# falownik_2.net
KiCad netlist of a schematic drawn in EAGLE
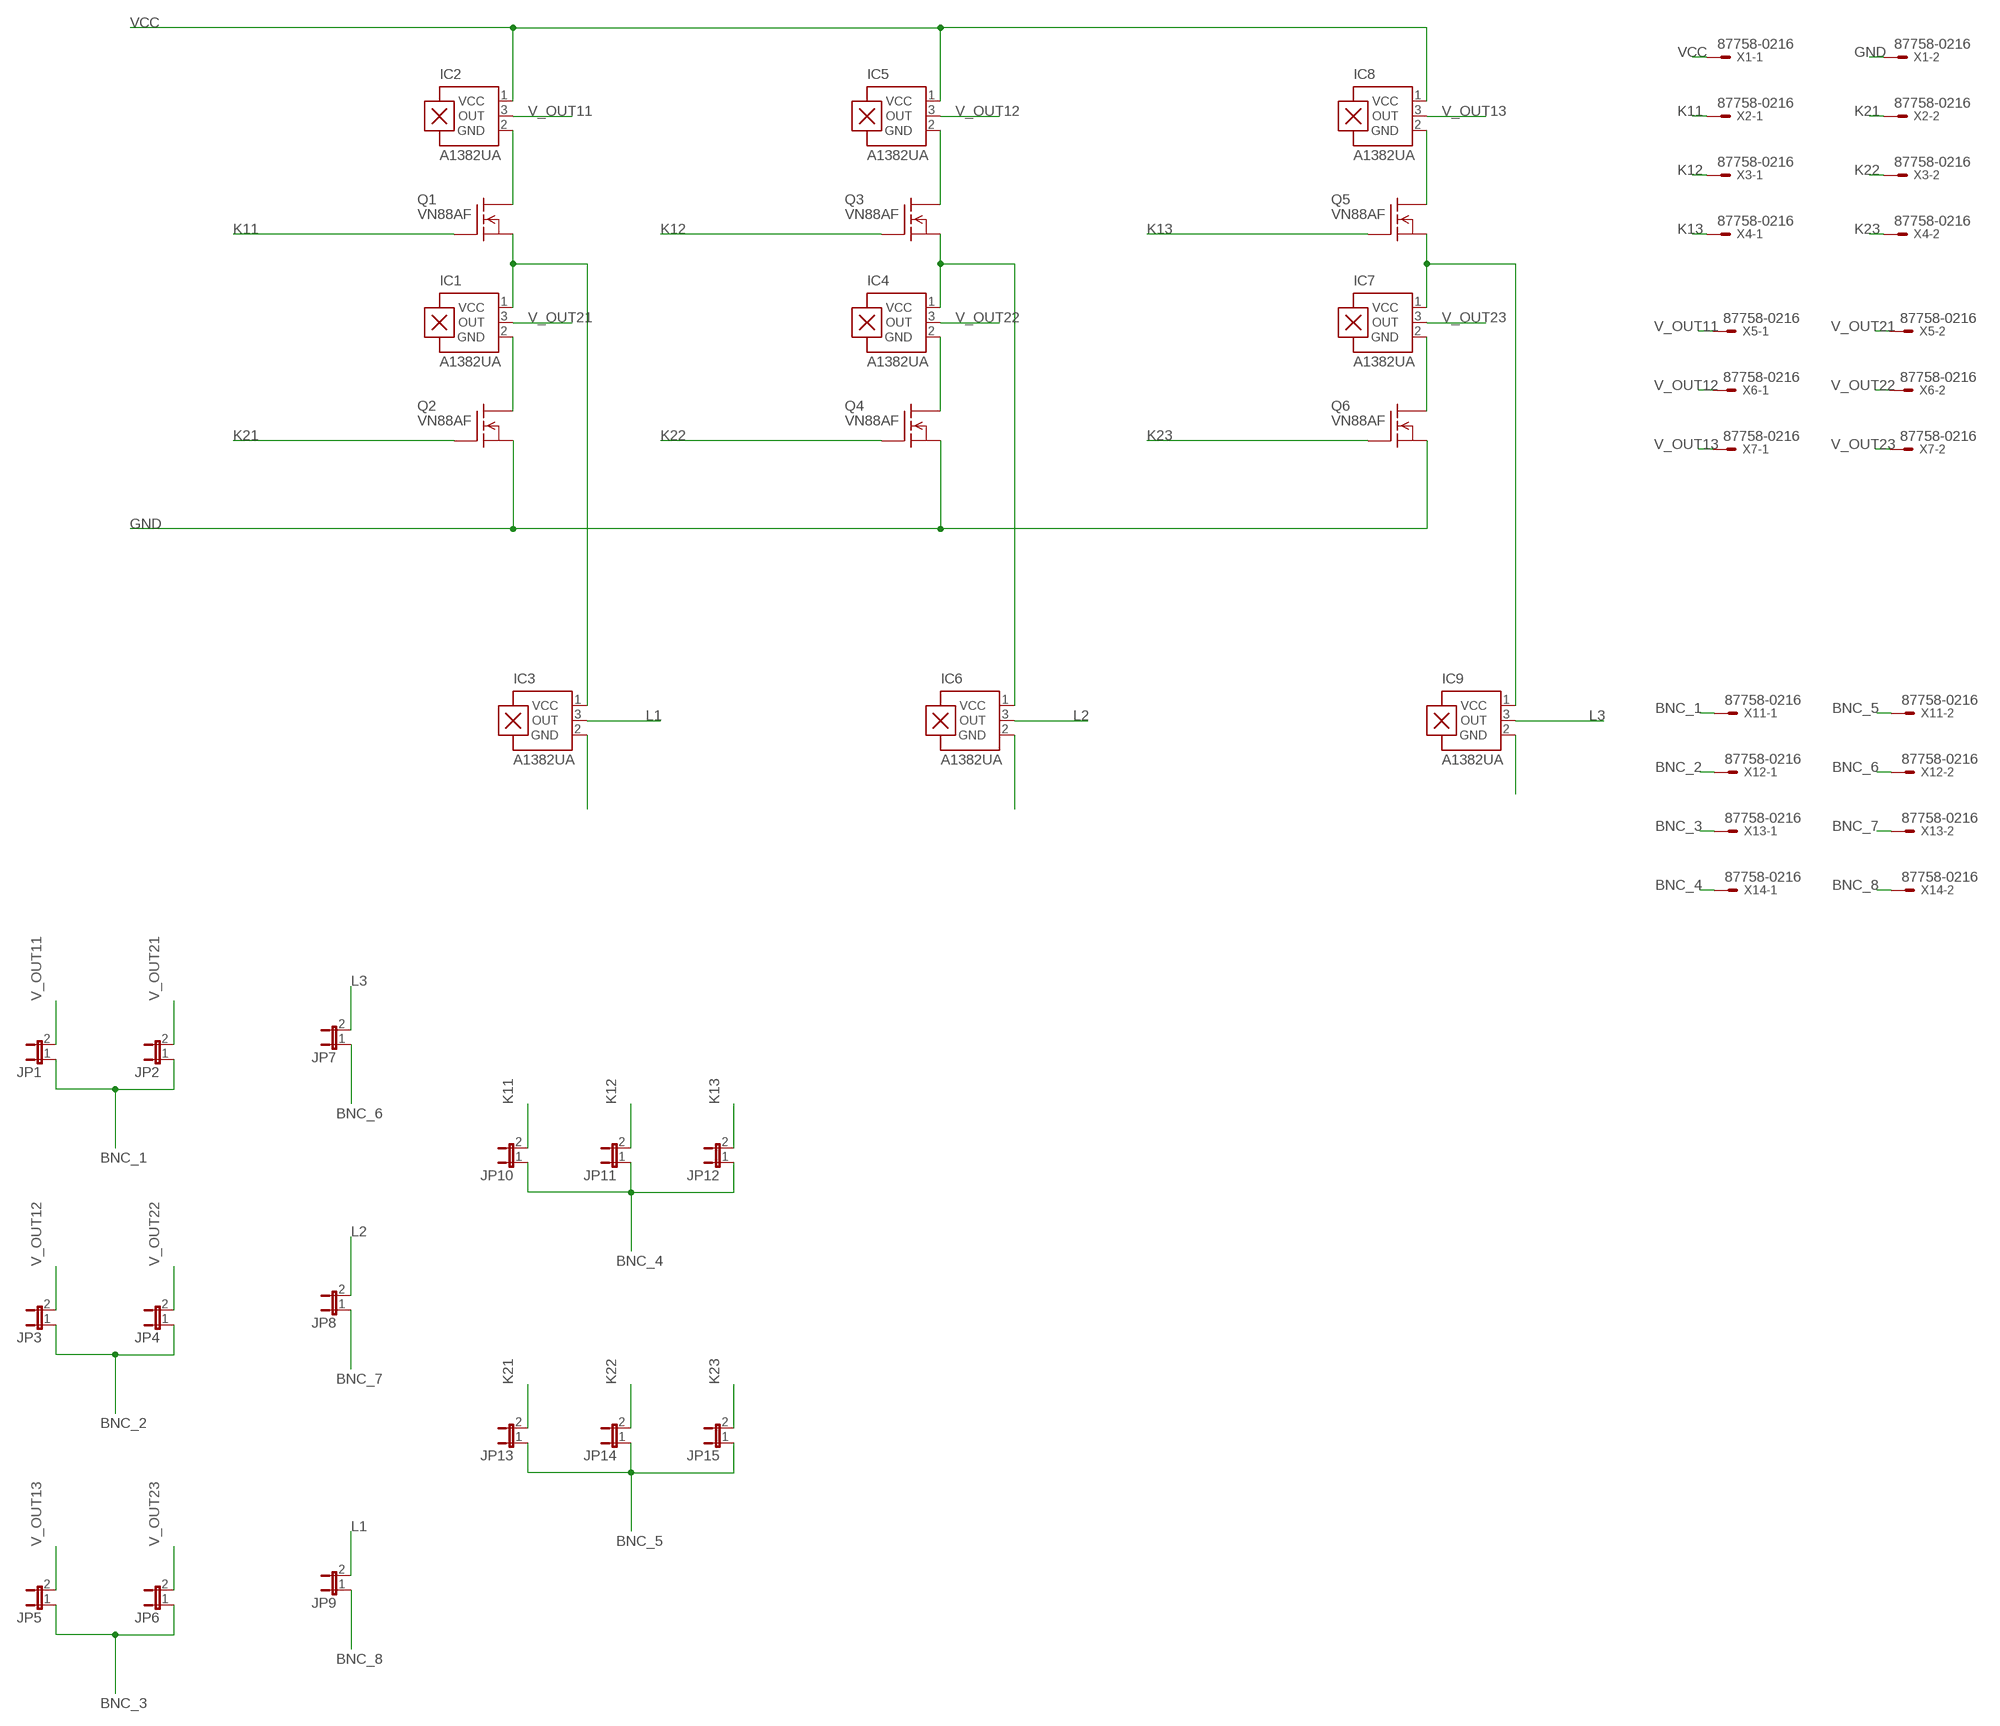
[diagram p0: schematic, sheet 1]

(export (version "E")
  (design (tool "Eeschema 10.0.6"))
  (components
    (comp (ref "IC1")
      (value "A1382UA")
      (footprint "eagle-import:SIP3-UA")
      (fields (field (name "MPN") "A1382LUA-T"))
      (libsource (lib "eagle-import") (part "A13?UA82"))
    )
    (comp (ref "IC2")
      (value "A1382UA")
      (footprint "eagle-import:SIP3-UA")
      (fields (field (name "MPN") "A1382LUA-T"))
      (libsource (lib "eagle-import") (part "A13?UA82"))
    )
    (comp (ref "IC3")
      (value "A1382UA")
      (footprint "eagle-import:SIP3-UA")
      (fields (field (name "MPN") "A1382LUA-T"))
      (libsource (lib "eagle-import") (part "A13?UA82"))
    )
    (comp (ref "IC4")
      (value "A1382UA")
      (footprint "eagle-import:SIP3-UA")
      (fields (field (name "MPN") "A1382LUA-T"))
      (libsource (lib "eagle-import") (part "A13?UA82"))
    )
    (comp (ref "IC5")
      (value "A1382UA")
      (footprint "eagle-import:SIP3-UA")
      (fields (field (name "MPN") "A1382LUA-T"))
      (libsource (lib "eagle-import") (part "A13?UA82"))
    )
    (comp (ref "IC6")
      (value "A1382UA")
      (footprint "eagle-import:SIP3-UA")
      (fields (field (name "MPN") "A1382LUA-T"))
      (libsource (lib "eagle-import") (part "A13?UA82"))
    )
    (comp (ref "IC7")
      (value "A1382UA")
      (footprint "eagle-import:SIP3-UA")
      (fields (field (name "MPN") "A1382LUA-T"))
      (libsource (lib "eagle-import") (part "A13?UA82"))
    )
    (comp (ref "IC8")
      (value "A1382UA")
      (footprint "eagle-import:SIP3-UA")
      (fields (field (name "MPN") "A1382LUA-T"))
      (libsource (lib "eagle-import") (part "A13?UA82"))
    )
    (comp (ref "IC9")
      (value "A1382UA")
      (footprint "eagle-import:SIP3-UA")
      (fields (field (name "MPN") "A1382LUA-T"))
      (libsource (lib "eagle-import") (part "A13?UA82"))
    )
    (comp (ref "JP1")
      (value "JP1E")
      (footprint "eagle-import:JP1")
      (libsource (lib "eagle-import") (part "JP1E"))
    )
    (comp (ref "JP2")
      (value "JP1E")
      (footprint "eagle-import:JP1")
      (libsource (lib "eagle-import") (part "JP1E"))
    )
    (comp (ref "JP3")
      (value "JP1E")
      (footprint "eagle-import:JP1")
      (libsource (lib "eagle-import") (part "JP1E"))
    )
    (comp (ref "JP4")
      (value "JP1E")
      (footprint "eagle-import:JP1")
      (libsource (lib "eagle-import") (part "JP1E"))
    )
    (comp (ref "JP5")
      (value "JP1E")
      (footprint "eagle-import:JP1")
      (libsource (lib "eagle-import") (part "JP1E"))
    )
    (comp (ref "JP6")
      (value "JP1E")
      (footprint "eagle-import:JP1")
      (libsource (lib "eagle-import") (part "JP1E"))
    )
    (comp (ref "JP7")
      (value "JP1E")
      (footprint "eagle-import:JP1")
      (libsource (lib "eagle-import") (part "JP1E"))
    )
    (comp (ref "JP8")
      (value "JP1E")
      (footprint "eagle-import:JP1")
      (libsource (lib "eagle-import") (part "JP1E"))
    )
    (comp (ref "JP9")
      (value "JP1E")
      (footprint "eagle-import:JP1")
      (libsource (lib "eagle-import") (part "JP1E"))
    )
    (comp (ref "JP10")
      (value "JP1E")
      (footprint "eagle-import:JP1")
      (libsource (lib "eagle-import") (part "JP1E"))
    )
    (comp (ref "JP11")
      (value "JP1E")
      (footprint "eagle-import:JP1")
      (libsource (lib "eagle-import") (part "JP1E"))
    )
    (comp (ref "JP12")
      (value "JP1E")
      (footprint "eagle-import:JP1")
      (libsource (lib "eagle-import") (part "JP1E"))
    )
    (comp (ref "JP13")
      (value "JP1E")
      (footprint "eagle-import:JP1")
      (libsource (lib "eagle-import") (part "JP1E"))
    )
    (comp (ref "JP14")
      (value "JP1E")
      (footprint "eagle-import:JP1")
      (libsource (lib "eagle-import") (part "JP1E"))
    )
    (comp (ref "JP15")
      (value "JP1E")
      (footprint "eagle-import:JP1")
      (libsource (lib "eagle-import") (part "JP1E"))
    )
    (comp (ref "Q1")
      (value "VN88AF")
      (footprint "eagle-import:TO202")
      (libsource (lib "eagle-import") (part "VN88AF"))
    )
    (comp (ref "Q2")
      (value "VN88AF")
      (footprint "eagle-import:TO202")
      (libsource (lib "eagle-import") (part "VN88AF"))
    )
    (comp (ref "Q3")
      (value "VN88AF")
      (footprint "eagle-import:TO202")
      (libsource (lib "eagle-import") (part "VN88AF"))
    )
    (comp (ref "Q4")
      (value "VN88AF")
      (footprint "eagle-import:TO202")
      (libsource (lib "eagle-import") (part "VN88AF"))
    )
    (comp (ref "Q5")
      (value "VN88AF")
      (footprint "eagle-import:TO202")
      (libsource (lib "eagle-import") (part "VN88AF"))
    )
    (comp (ref "Q6")
      (value "VN88AF")
      (footprint "eagle-import:TO202")
      (libsource (lib "eagle-import") (part "VN88AF"))
    )
    (comp (ref "X1")
      (value "87758-0216")
      (footprint "eagle-import:87758-0216")
      (fields (field (name "MF") "MOLEX"))
      (libsource (lib "eagle-import") (part "87758-0216"))
    )
    (comp (ref "X2")
      (value "87758-0216")
      (footprint "eagle-import:87758-0216")
      (fields (field (name "MF") "MOLEX"))
      (libsource (lib "eagle-import") (part "87758-0216"))
    )
    (comp (ref "X3")
      (value "87758-0216")
      (footprint "eagle-import:87758-0216")
      (fields (field (name "MF") "MOLEX"))
      (libsource (lib "eagle-import") (part "87758-0216"))
    )
    (comp (ref "X4")
      (value "87758-0216")
      (footprint "eagle-import:87758-0216")
      (fields (field (name "MF") "MOLEX"))
      (libsource (lib "eagle-import") (part "87758-0216"))
    )
    (comp (ref "X5")
      (value "87758-0216")
      (footprint "eagle-import:87758-0216")
      (fields (field (name "MF") "MOLEX"))
      (libsource (lib "eagle-import") (part "87758-0216"))
    )
    (comp (ref "X6")
      (value "87758-0216")
      (footprint "eagle-import:87758-0216")
      (fields (field (name "MF") "MOLEX"))
      (libsource (lib "eagle-import") (part "87758-0216"))
    )
    (comp (ref "X7")
      (value "87758-0216")
      (footprint "eagle-import:87758-0216")
      (fields (field (name "MF") "MOLEX"))
      (libsource (lib "eagle-import") (part "87758-0216"))
    )
    (comp (ref "X11")
      (value "87758-0216")
      (footprint "eagle-import:87758-0216")
      (fields (field (name "MF") "MOLEX"))
      (libsource (lib "eagle-import") (part "87758-0216"))
    )
    (comp (ref "X12")
      (value "87758-0216")
      (footprint "eagle-import:87758-0216")
      (fields (field (name "MF") "MOLEX"))
      (libsource (lib "eagle-import") (part "87758-0216"))
    )
    (comp (ref "X13")
      (value "87758-0216")
      (footprint "eagle-import:87758-0216")
      (fields (field (name "MF") "MOLEX"))
      (libsource (lib "eagle-import") (part "87758-0216"))
    )
    (comp (ref "X14")
      (value "87758-0216")
      (footprint "eagle-import:87758-0216")
      (fields (field (name "MF") "MOLEX"))
      (libsource (lib "eagle-import") (part "87758-0216"))
    )
  )
  (nets
    (net (code "1") (name "/BNC_1") (class "Default")
      (node (ref "JP1") (pin "1") (pinfunction "1_1") (pintype "passive"))
      (node (ref "JP2") (pin "1") (pinfunction "1_1") (pintype "passive"))
      (node (ref "X11") (pin "1") (pinfunction "S_1") (pintype "passive"))
    )
    (net (code "2") (name "/BNC_2") (class "Default")
      (node (ref "JP3") (pin "1") (pinfunction "1_1") (pintype "passive"))
      (node (ref "JP4") (pin "1") (pinfunction "1_1") (pintype "passive"))
      (node (ref "X12") (pin "1") (pinfunction "S_1") (pintype "passive"))
    )
    (net (code "3") (name "/BNC_3") (class "Default")
      (node (ref "JP5") (pin "1") (pinfunction "1_1") (pintype "passive"))
      (node (ref "JP6") (pin "1") (pinfunction "1_1") (pintype "passive"))
      (node (ref "X13") (pin "1") (pinfunction "S_1") (pintype "passive"))
    )
    (net (code "4") (name "/BNC_4") (class "Default")
      (node (ref "JP10") (pin "1") (pinfunction "1_1") (pintype "passive"))
      (node (ref "JP11") (pin "1") (pinfunction "1_1") (pintype "passive"))
      (node (ref "JP12") (pin "1") (pinfunction "1_1") (pintype "passive"))
      (node (ref "X14") (pin "1") (pinfunction "S_1") (pintype "passive"))
    )
    (net (code "5") (name "/BNC_5") (class "Default")
      (node (ref "JP13") (pin "1") (pinfunction "1_1") (pintype "passive"))
      (node (ref "JP14") (pin "1") (pinfunction "1_1") (pintype "passive"))
      (node (ref "JP15") (pin "1") (pinfunction "1_1") (pintype "passive"))
      (node (ref "X11") (pin "2") (pinfunction "S_2") (pintype "passive"))
    )
    (net (code "6") (name "/BNC_6") (class "Default")
      (node (ref "JP7") (pin "1") (pinfunction "1_1") (pintype "passive"))
      (node (ref "X12") (pin "2") (pinfunction "S_2") (pintype "passive"))
    )
    (net (code "7") (name "/BNC_7") (class "Default")
      (node (ref "JP8") (pin "1") (pinfunction "1_1") (pintype "passive"))
      (node (ref "X13") (pin "2") (pinfunction "S_2") (pintype "passive"))
    )
    (net (code "8") (name "/BNC_8") (class "Default")
      (node (ref "JP9") (pin "1") (pinfunction "1_1") (pintype "passive"))
      (node (ref "X14") (pin "2") (pinfunction "S_2") (pintype "passive"))
    )
    (net (code "9") (name "/GND") (class "Default")
      (node (ref "Q2") (pin "1") (pinfunction "S_1") (pintype "passive"))
      (node (ref "Q4") (pin "1") (pinfunction "S_1") (pintype "passive"))
      (node (ref "Q6") (pin "1") (pinfunction "S_1") (pintype "passive"))
      (node (ref "X1") (pin "2") (pinfunction "S_2") (pintype "passive"))
    )
    (net (code "10") (name "/K11") (class "Default")
      (node (ref "JP10") (pin "2") (pinfunction "2_2") (pintype "passive"))
      (node (ref "Q1") (pin "2") (pinfunction "G_2") (pintype "passive"))
      (node (ref "X2") (pin "1") (pinfunction "S_1") (pintype "passive"))
    )
    (net (code "11") (name "/K12") (class "Default")
      (node (ref "JP11") (pin "2") (pinfunction "2_2") (pintype "passive"))
      (node (ref "Q3") (pin "2") (pinfunction "G_2") (pintype "passive"))
      (node (ref "X3") (pin "1") (pinfunction "S_1") (pintype "passive"))
    )
    (net (code "12") (name "/K13") (class "Default")
      (node (ref "JP12") (pin "2") (pinfunction "2_2") (pintype "passive"))
      (node (ref "Q5") (pin "2") (pinfunction "G_2") (pintype "passive"))
      (node (ref "X4") (pin "1") (pinfunction "S_1") (pintype "passive"))
    )
    (net (code "13") (name "/K21") (class "Default")
      (node (ref "JP13") (pin "2") (pinfunction "2_2") (pintype "passive"))
      (node (ref "Q2") (pin "2") (pinfunction "G_2") (pintype "passive"))
      (node (ref "X2") (pin "2") (pinfunction "S_2") (pintype "passive"))
    )
    (net (code "14") (name "/K22") (class "Default")
      (node (ref "JP14") (pin "2") (pinfunction "2_2") (pintype "passive"))
      (node (ref "Q4") (pin "2") (pinfunction "G_2") (pintype "passive"))
      (node (ref "X3") (pin "2") (pinfunction "S_2") (pintype "passive"))
    )
    (net (code "15") (name "/K23") (class "Default")
      (node (ref "JP15") (pin "2") (pinfunction "2_2") (pintype "passive"))
      (node (ref "Q6") (pin "2") (pinfunction "G_2") (pintype "passive"))
      (node (ref "X4") (pin "2") (pinfunction "S_2") (pintype "passive"))
    )
    (net (code "16") (name "/L1") (class "Default")
      (node (ref "IC3") (pin "3") (pinfunction "OUT_3") (pintype "output"))
      (node (ref "JP9") (pin "2") (pinfunction "2_2") (pintype "passive"))
    )
    (net (code "17") (name "/L2") (class "Default")
      (node (ref "IC6") (pin "3") (pinfunction "OUT_3") (pintype "output"))
      (node (ref "JP8") (pin "2") (pinfunction "2_2") (pintype "passive"))
    )
    (net (code "18") (name "/L3") (class "Default")
      (node (ref "IC9") (pin "3") (pinfunction "OUT_3") (pintype "output"))
      (node (ref "JP7") (pin "2") (pinfunction "2_2") (pintype "passive"))
    )
    (net (code "19") (name "/VCC") (class "Default")
      (node (ref "IC2") (pin "1") (pinfunction "VCC_1") (pintype "power_in"))
      (node (ref "IC5") (pin "1") (pinfunction "VCC_1") (pintype "power_in"))
      (node (ref "IC8") (pin "1") (pinfunction "VCC_1") (pintype "power_in"))
      (node (ref "X1") (pin "1") (pinfunction "S_1") (pintype "passive"))
    )
    (net (code "20") (name "/V_OUT11") (class "Default")
      (node (ref "IC2") (pin "3") (pinfunction "OUT_3") (pintype "output"))
      (node (ref "JP1") (pin "2") (pinfunction "2_2") (pintype "passive"))
      (node (ref "X5") (pin "1") (pinfunction "S_1") (pintype "passive"))
    )
    (net (code "21") (name "/V_OUT12") (class "Default")
      (node (ref "IC5") (pin "3") (pinfunction "OUT_3") (pintype "output"))
      (node (ref "JP3") (pin "2") (pinfunction "2_2") (pintype "passive"))
      (node (ref "X6") (pin "1") (pinfunction "S_1") (pintype "passive"))
    )
    (net (code "22") (name "/V_OUT13") (class "Default")
      (node (ref "IC8") (pin "3") (pinfunction "OUT_3") (pintype "output"))
      (node (ref "JP5") (pin "2") (pinfunction "2_2") (pintype "passive"))
      (node (ref "X7") (pin "1") (pinfunction "S_1") (pintype "passive"))
    )
    (net (code "23") (name "/V_OUT21") (class "Default")
      (node (ref "IC1") (pin "3") (pinfunction "OUT_3") (pintype "output"))
      (node (ref "JP2") (pin "2") (pinfunction "2_2") (pintype "passive"))
      (node (ref "X5") (pin "2") (pinfunction "S_2") (pintype "passive"))
    )
    (net (code "24") (name "/V_OUT22") (class "Default")
      (node (ref "IC4") (pin "3") (pinfunction "OUT_3") (pintype "output"))
      (node (ref "JP4") (pin "2") (pinfunction "2_2") (pintype "passive"))
      (node (ref "X6") (pin "2") (pinfunction "S_2") (pintype "passive"))
    )
    (net (code "25") (name "/V_OUT23") (class "Default")
      (node (ref "IC7") (pin "3") (pinfunction "OUT_3") (pintype "output"))
      (node (ref "JP6") (pin "2") (pinfunction "2_2") (pintype "passive"))
      (node (ref "X7") (pin "2") (pinfunction "S_2") (pintype "passive"))
    )
    (net (code "26") (name "Net-(IC1-GND)") (class "Default")
      (node (ref "IC1") (pin "2") (pinfunction "GND_2") (pintype "power_in"))
      (node (ref "Q2") (pin "3") (pinfunction "D_3") (pintype "passive"))
    )
    (net (code "27") (name "Net-(IC1-VCC)") (class "Default")
      (node (ref "IC1") (pin "1") (pinfunction "VCC_1") (pintype "power_in"))
      (node (ref "IC3") (pin "1") (pinfunction "VCC_1") (pintype "power_in"))
      (node (ref "Q1") (pin "1") (pinfunction "S_1") (pintype "passive"))
    )
    (net (code "28") (name "Net-(IC2-GND)") (class "Default")
      (node (ref "IC2") (pin "2") (pinfunction "GND_2") (pintype "power_in"))
      (node (ref "Q1") (pin "3") (pinfunction "D_3") (pintype "passive"))
    )
    (net (code "29") (name "Net-(IC4-GND)") (class "Default")
      (node (ref "IC4") (pin "2") (pinfunction "GND_2") (pintype "power_in"))
      (node (ref "Q4") (pin "3") (pinfunction "D_3") (pintype "passive"))
    )
    (net (code "30") (name "Net-(IC4-VCC)") (class "Default")
      (node (ref "IC4") (pin "1") (pinfunction "VCC_1") (pintype "power_in"))
      (node (ref "IC6") (pin "1") (pinfunction "VCC_1") (pintype "power_in"))
      (node (ref "Q3") (pin "1") (pinfunction "S_1") (pintype "passive"))
    )
    (net (code "31") (name "Net-(IC5-GND)") (class "Default")
      (node (ref "IC5") (pin "2") (pinfunction "GND_2") (pintype "power_in"))
      (node (ref "Q3") (pin "3") (pinfunction "D_3") (pintype "passive"))
    )
    (net (code "32") (name "Net-(IC7-GND)") (class "Default")
      (node (ref "IC7") (pin "2") (pinfunction "GND_2") (pintype "power_in"))
      (node (ref "Q6") (pin "3") (pinfunction "D_3") (pintype "passive"))
    )
    (net (code "33") (name "Net-(IC7-VCC)") (class "Default")
      (node (ref "IC7") (pin "1") (pinfunction "VCC_1") (pintype "power_in"))
      (node (ref "IC9") (pin "1") (pinfunction "VCC_1") (pintype "power_in"))
      (node (ref "Q5") (pin "1") (pinfunction "S_1") (pintype "passive"))
    )
    (net (code "34") (name "Net-(IC8-GND)") (class "Default")
      (node (ref "IC8") (pin "2") (pinfunction "GND_2") (pintype "power_in"))
      (node (ref "Q5") (pin "3") (pinfunction "D_3") (pintype "passive"))
    )
    (net (code "35") (name "unconnected-(IC3-GND-Pad2)") (class "Default")
      (node (ref "IC3") (pin "2") (pinfunction "GND_2") (pintype "power_in"))
    )
    (net (code "36") (name "unconnected-(IC6-GND-Pad2)") (class "Default")
      (node (ref "IC6") (pin "2") (pinfunction "GND_2") (pintype "power_in"))
    )
    (net (code "37") (name "unconnected-(IC9-GND-Pad2)") (class "Default")
      (node (ref "IC9") (pin "2") (pinfunction "GND_2") (pintype "power_in"))
    )
  )
)
